# TB-S5D5_p03_MCU-v1_2.net
KiCad netlist of a schematic drawn in Altium Designer
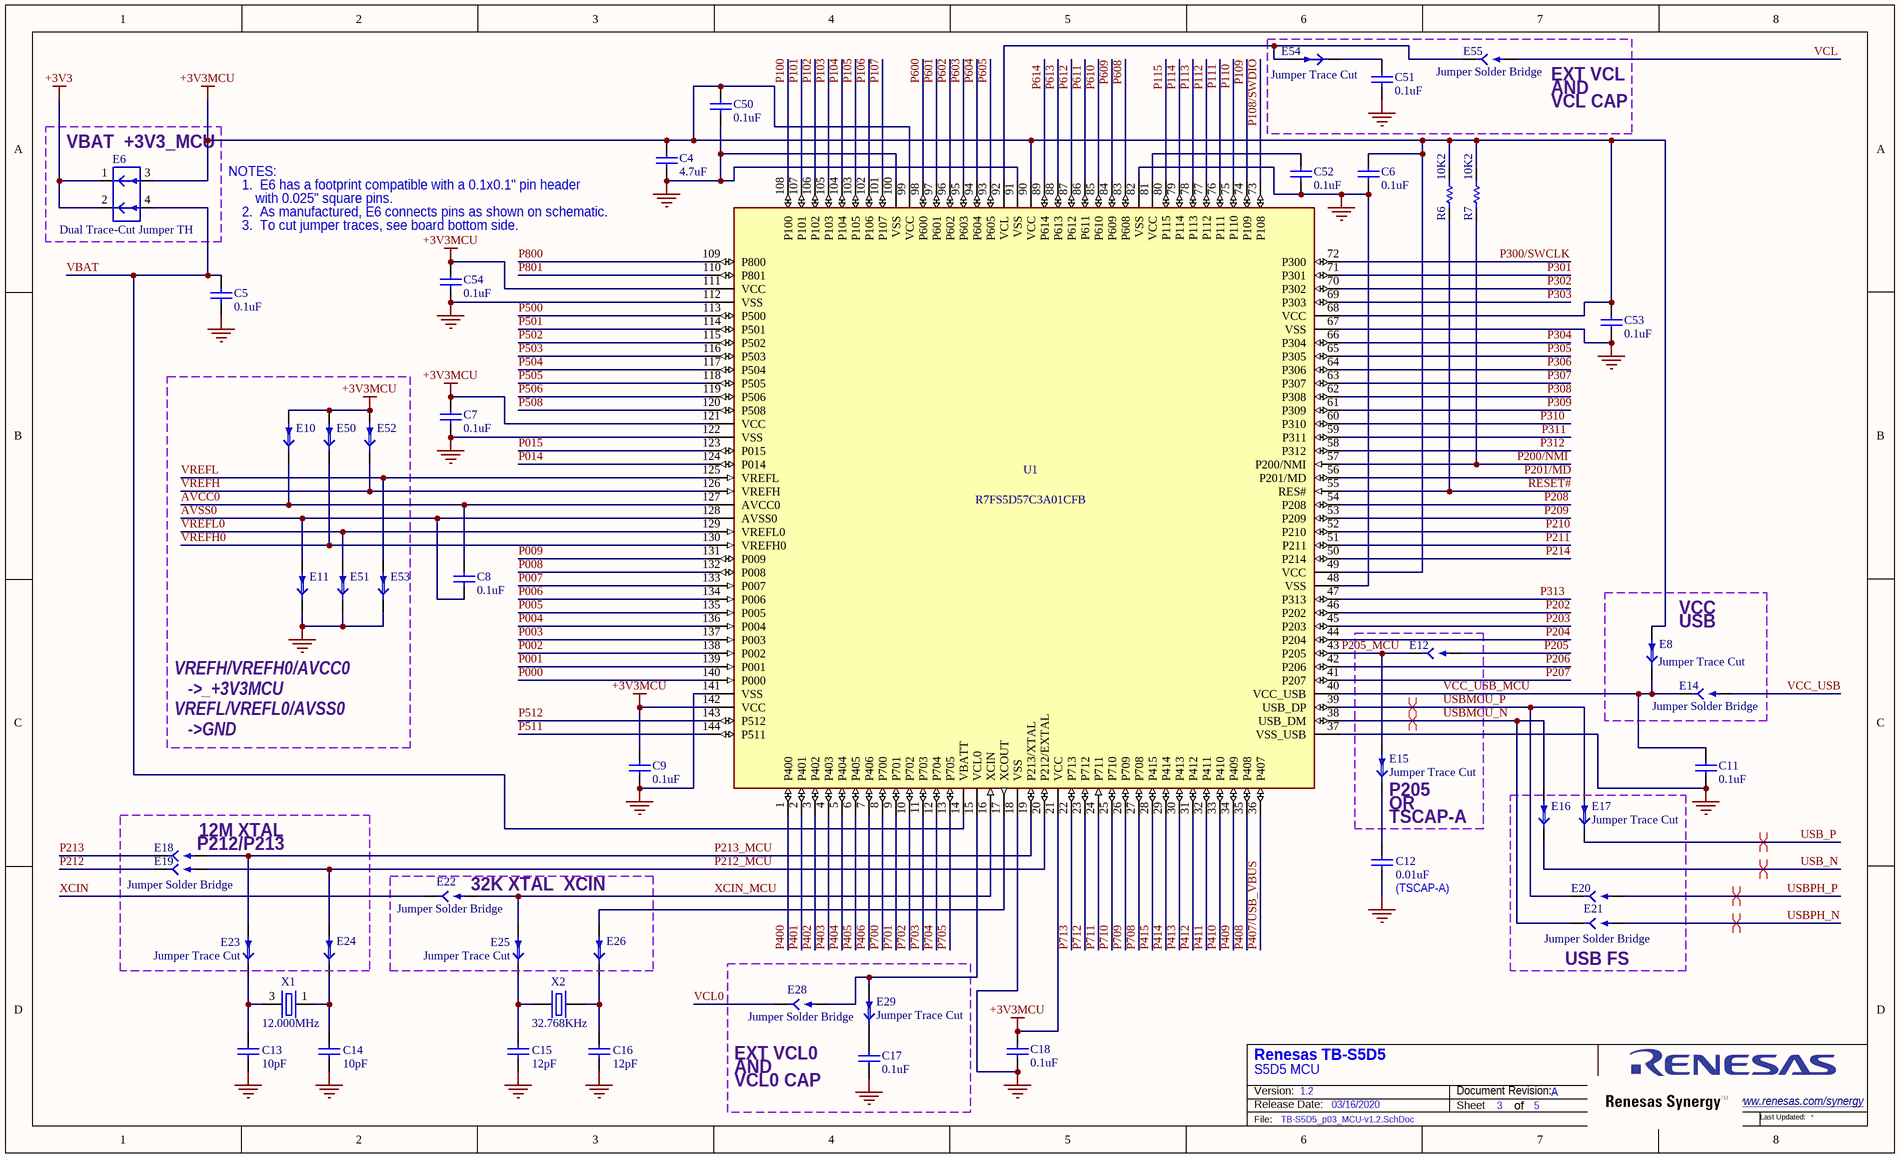
[diagram p0: TB-S5D5_p03_MCU-v1.2.SchDoc]

(export (version "E")
  (design (tool "Eeschema 10.0.6"))
  (components
    (comp (ref "C4")
      (value "CAP-000043-01")
      (footprint "CAPC0603-01")
      (description "Ceramic Chip Capacitor 0603 4.7uF 6.3V")
      (fields
        (field (name "MANUFACTURER") "Samsung")
        (field (name "MFG PART NUMBER") "CL10A475KQ8NNNL")
        (field (name "CAPACITANCE") "4.7uF")
      )
      (libsource (lib "Capacitors") (part "CAP-000043-01"))
    )
    (comp (ref "C5")
      (value "CAP-000029-01")
      (footprint "CAPC0603-01")
      (description "Ceramic Chip Capacitor 0603 0.1uF 50V")
      (fields
        (field (name "MANUFACTURER") "Samsung")
        (field (name "MFG PART NUMBER") "CL10B104KB8NNNC")
        (field (name "CAPACITANCE") "0.1uF")
      )
      (libsource (lib "Capacitors") (part "CAP-000029-01"))
    )
    (comp (ref "C6")
      (value "CAP-000029-01")
      (footprint "CAPC0603-01")
      (description "Ceramic Chip Capacitor 0603 0.1uF 50V")
      (fields
        (field (name "MANUFACTURER") "Samsung")
        (field (name "MFG PART NUMBER") "CL10B104KB8NNNC")
        (field (name "CAPACITANCE") "0.1uF")
      )
      (libsource (lib "Capacitors") (part "CAP-000029-01"))
    )
    (comp (ref "C7")
      (value "CAP-000029-01")
      (footprint "CAPC0603-01")
      (description "Ceramic Chip Capacitor 0603 0.1uF 50V")
      (fields
        (field (name "MANUFACTURER") "Samsung")
        (field (name "MFG PART NUMBER") "CL10B104KB8NNNC")
        (field (name "CAPACITANCE") "0.1uF")
      )
      (libsource (lib "Capacitors") (part "CAP-000029-01"))
    )
    (comp (ref "C8")
      (value "CAP-000029-01")
      (footprint "CAPC0603-01")
      (description "Ceramic Chip Capacitor 0603 0.1uF 50V")
      (fields
        (field (name "MANUFACTURER") "Samsung")
        (field (name "MFG PART NUMBER") "CL10B104KB8NNNC")
        (field (name "CAPACITANCE") "0.1uF")
      )
      (libsource (lib "Capacitors") (part "CAP-000029-01"))
    )
    (comp (ref "C9")
      (value "CAP-000029-01")
      (footprint "CAPC0603-01")
      (description "Ceramic Chip Capacitor 0603 0.1uF 50V")
      (fields
        (field (name "MANUFACTURER") "Samsung")
        (field (name "MFG PART NUMBER") "CL10B104KB8NNNC")
        (field (name "CAPACITANCE") "0.1uF")
      )
      (libsource (lib "Capacitors") (part "CAP-000029-01"))
    )
    (comp (ref "C11")
      (value "CAP-000029-01")
      (footprint "CAPC0603-01")
      (description "Ceramic Chip Capacitor 0603 0.1uF 50V")
      (fields
        (field (name "MANUFACTURER") "Samsung")
        (field (name "MFG PART NUMBER") "CL10B104KB8NNNC")
        (field (name "CAPACITANCE") "0.1uF")
      )
      (libsource (lib "Capacitors") (part "CAP-000029-01"))
    )
    (comp (ref "C12")
      (value "CAP-000062-01")
      (footprint "CAPC0402-01")
      (description "Ceramic Chip Capacitor 0402 0.01uF 50V")
      (fields
        (field (name "MANUFACTURER") "Samsung")
        (field (name "MFG PART NUMBER") "CL05B103KB5NNNC")
        (field (name "CAPACITANCE") "0.01uF")
      )
      (libsource (lib "Capacitors") (part "CAP-000062-01"))
    )
    (comp (ref "C13")
      (value "CAP-000081-01")
      (footprint "CAPC0201-01")
      (description "Ceramic Chip Capacitor 0201 10pF 25V")
      (fields
        (field (name "MANUFACTURER") "Samsung")
        (field (name "MFG PART NUMBER") "CL03C100DA3GNNC")
        (field (name "CAPACITANCE") "10pF")
      )
      (libsource (lib "Capacitors") (part "CAP-000081-01"))
    )
    (comp (ref "C14")
      (value "CAP-000081-01")
      (footprint "CAPC0201-01")
      (description "Ceramic Chip Capacitor 0201 10pF 25V")
      (fields
        (field (name "MANUFACTURER") "Samsung")
        (field (name "MFG PART NUMBER") "CL03C100DA3GNNC")
        (field (name "CAPACITANCE") "10pF")
      )
      (libsource (lib "Capacitors") (part "CAP-000081-01"))
    )
    (comp (ref "C15")
      (value "CAP-000059-01")
      (footprint "CAPC0402-01")
      (description "Ceramic Chip Capacitor 0402 12pF 50V")
      (fields
        (field (name "MANUFACTURER") "Samsung")
        (field (name "MFG PART NUMBER") "CL05C120JB5NNNC")
        (field (name "CAPACITANCE") "12pF")
      )
      (libsource (lib "Capacitors") (part "CAP-000059-01"))
    )
    (comp (ref "C16")
      (value "CAP-000059-01")
      (footprint "CAPC0402-01")
      (description "Ceramic Chip Capacitor 0402 12pF 50V")
      (fields
        (field (name "MANUFACTURER") "Samsung")
        (field (name "MFG PART NUMBER") "CL05C120JB5NNNC")
        (field (name "CAPACITANCE") "12pF")
      )
      (libsource (lib "Capacitors") (part "CAP-000059-01"))
    )
    (comp (ref "C17")
      (value "CAP-000029-01")
      (footprint "CAPC0603-01")
      (description "Ceramic Chip Capacitor 0603 0.1uF 50V")
      (fields
        (field (name "MANUFACTURER") "Samsung")
        (field (name "MFG PART NUMBER") "CL10B104KB8NNNC")
        (field (name "CAPACITANCE") "0.1uF")
      )
      (libsource (lib "Capacitors") (part "CAP-000029-01"))
    )
    (comp (ref "C18")
      (value "CAP-000029-01")
      (footprint "CAPC0603-01")
      (description "Ceramic Chip Capacitor 0603 0.1uF 50V")
      (fields
        (field (name "MANUFACTURER") "Samsung")
        (field (name "MFG PART NUMBER") "CL10B104KB8NNNC")
        (field (name "CAPACITANCE") "0.1uF")
      )
      (libsource (lib "Capacitors") (part "CAP-000029-01"))
    )
    (comp (ref "C50")
      (value "CAP-000029-01")
      (footprint "CAPC0603-01")
      (description "Ceramic Chip Capacitor 0603 0.1uF 50V")
      (fields
        (field (name "MANUFACTURER") "Samsung")
        (field (name "MFG PART NUMBER") "CL10B104KB8NNNC")
        (field (name "CAPACITANCE") "0.1uF")
      )
      (libsource (lib "Capacitors") (part "CAP-000029-01"))
    )
    (comp (ref "C51")
      (value "CAP-000029-01")
      (footprint "CAPC0603-01")
      (description "Ceramic Chip Capacitor 0603 0.1uF 50V")
      (fields
        (field (name "MANUFACTURER") "Samsung")
        (field (name "MFG PART NUMBER") "CL10B104KB8NNNC")
        (field (name "CAPACITANCE") "0.1uF")
      )
      (libsource (lib "Capacitors") (part "CAP-000029-01"))
    )
    (comp (ref "C52")
      (value "CAP-000029-01")
      (footprint "CAPC0603-01")
      (description "Ceramic Chip Capacitor 0603 0.1uF 50V")
      (fields
        (field (name "MANUFACTURER") "Samsung")
        (field (name "MFG PART NUMBER") "CL10B104KB8NNNC")
        (field (name "CAPACITANCE") "0.1uF")
      )
      (libsource (lib "Capacitors") (part "CAP-000029-01"))
    )
    (comp (ref "C53")
      (value "CAP-000029-01")
      (footprint "CAPC0603-01")
      (description "Ceramic Chip Capacitor 0603 0.1uF 50V")
      (fields
        (field (name "MANUFACTURER") "Samsung")
        (field (name "MFG PART NUMBER") "CL10B104KB8NNNC")
        (field (name "CAPACITANCE") "0.1uF")
      )
      (libsource (lib "Capacitors") (part "CAP-000029-01"))
    )
    (comp (ref "C54")
      (value "CAP-000029-01")
      (footprint "CAPC0603-01")
      (description "Ceramic Chip Capacitor 0603 0.1uF 50V")
      (fields
        (field (name "MANUFACTURER") "Samsung")
        (field (name "MFG PART NUMBER") "CL10B104KB8NNNC")
        (field (name "CAPACITANCE") "0.1uF")
      )
      (libsource (lib "Capacitors") (part "CAP-000029-01"))
    )
    (comp (ref "E6")
      (value "Dual Trace-Cut Jumper TH")
      (footprint "E_2x2pTH-TC100mil")
      (description "Trace-Cut Jumper pair, pins 1->3 & 2->4 connected")
      (libsource (lib "TB_SpecialLib") (part "E_JmpTCx2"))
    )
    (comp (ref "E8")
      (value "Jumper Trace Cut")
      (footprint "E_PadsTraceCut0805")
      (description "Pads on PCB with Trace Between for Cutting to isolate")
      (libsource (lib "TB_SpecialLib") (part "E_JmpTraceCut"))
    )
    (comp (ref "E10")
      (value "Jumper Trace Cut")
      (footprint "E_PadsTraceCut0805")
      (description "Pads on PCB with Trace Between for Cutting to isolate")
      (libsource (lib "TB_SpecialLib") (part "E_JmpTraceCut"))
    )
    (comp (ref "E11")
      (value "Jumper Trace Cut")
      (footprint "E_PadsTraceCut0805")
      (description "Pads on PCB with Trace Between for Cutting to isolate")
      (libsource (lib "TB_SpecialLib") (part "E_JmpTraceCut"))
    )
    (comp (ref "E12")
      (value "Jumper Solder Bridge")
      (footprint "E_PadsSplit0805")
      (description "Pads on PCB with Narrow Gap to allow Solder Bridging")
      (libsource (lib "TB_SpecialLib") (part "E_JmpSldrBridge"))
    )
    (comp (ref "E14")
      (value "Jumper Solder Bridge")
      (footprint "E_PadsSplit0805")
      (description "Pads on PCB with Narrow Gap to allow Solder Bridging")
      (libsource (lib "TB_SpecialLib") (part "E_JmpSldrBridge"))
    )
    (comp (ref "E15")
      (value "Jumper Trace Cut")
      (footprint "E_PadsTraceCut0805")
      (description "Pads on PCB with Trace Between for Cutting to isolate")
      (libsource (lib "TB_SpecialLib") (part "E_JmpTraceCut"))
    )
    (comp (ref "E16")
      (value "Jumper Trace Cut")
      (footprint "E_PadsTraceCut0805")
      (description "Pads on PCB with Trace Between for Cutting to isolate")
      (libsource (lib "TB_SpecialLib") (part "E_JmpTraceCut"))
    )
    (comp (ref "E17")
      (value "Jumper Trace Cut")
      (footprint "E_PadsTraceCut0805")
      (description "Pads on PCB with Trace Between for Cutting to isolate")
      (libsource (lib "TB_SpecialLib") (part "E_JmpTraceCut"))
    )
    (comp (ref "E18")
      (value "Jumper Solder Bridge")
      (footprint "E_PadsSplit0805")
      (description "Pads on PCB with Narrow Gap to allow Solder Bridging")
      (libsource (lib "TB_SpecialLib") (part "E_JmpSldrBridge"))
    )
    (comp (ref "E19")
      (value "Jumper Solder Bridge")
      (footprint "E_PadsSplit0805")
      (description "Pads on PCB with Narrow Gap to allow Solder Bridging")
      (libsource (lib "TB_SpecialLib") (part "E_JmpSldrBridge"))
    )
    (comp (ref "E20")
      (value "Jumper Solder Bridge")
      (footprint "E_PadsSplit0805")
      (description "Pads on PCB with Narrow Gap to allow Solder Bridging")
      (libsource (lib "TB_SpecialLib") (part "E_JmpSldrBridge"))
    )
    (comp (ref "E21")
      (value "Jumper Solder Bridge")
      (footprint "E_PadsSplit0805")
      (description "Pads on PCB with Narrow Gap to allow Solder Bridging")
      (libsource (lib "TB_SpecialLib") (part "E_JmpSldrBridge"))
    )
    (comp (ref "E22")
      (value "Jumper Solder Bridge")
      (footprint "E_PadsSplit0805")
      (description "Pads on PCB with Narrow Gap to allow Solder Bridging")
      (libsource (lib "TB_SpecialLib") (part "E_JmpSldrBridge"))
    )
    (comp (ref "E23")
      (value "Jumper Trace Cut")
      (footprint "E_PadsTraceCut0805")
      (description "Pads on PCB with Trace Between for Cutting to isolate")
      (libsource (lib "TB_SpecialLib") (part "E_JmpTraceCut"))
    )
    (comp (ref "E24")
      (value "Jumper Trace Cut")
      (footprint "E_PadsTraceCut0805")
      (description "Pads on PCB with Trace Between for Cutting to isolate")
      (libsource (lib "TB_SpecialLib") (part "E_JmpTraceCut"))
    )
    (comp (ref "E25")
      (value "Jumper Trace Cut")
      (footprint "E_PadsTraceCut0805")
      (description "Pads on PCB with Trace Between for Cutting to isolate")
      (libsource (lib "TB_SpecialLib") (part "E_JmpTraceCut"))
    )
    (comp (ref "E26")
      (value "Jumper Trace Cut")
      (footprint "E_PadsTraceCut0805")
      (description "Pads on PCB with Trace Between for Cutting to isolate")
      (libsource (lib "TB_SpecialLib") (part "E_JmpTraceCut"))
    )
    (comp (ref "E28")
      (value "Jumper Solder Bridge")
      (footprint "E_PadsSplit0805")
      (description "Pads on PCB with Narrow Gap to allow Solder Bridging")
      (libsource (lib "TB_SpecialLib") (part "E_JmpSldrBridge"))
    )
    (comp (ref "E29")
      (value "Jumper Trace Cut")
      (footprint "E_PadsTraceCut0805")
      (description "Pads on PCB with Trace Between for Cutting to isolate")
      (libsource (lib "TB_SpecialLib") (part "E_JmpTraceCut"))
    )
    (comp (ref "E50")
      (value "Jumper Trace Cut")
      (footprint "E_PadsTraceCut0805")
      (description "Pads on PCB with Trace Between for Cutting to isolate")
      (libsource (lib "TB_SpecialLib") (part "E_JmpTraceCut"))
    )
    (comp (ref "E51")
      (value "Jumper Trace Cut")
      (footprint "E_PadsTraceCut0805")
      (description "Pads on PCB with Trace Between for Cutting to isolate")
      (libsource (lib "TB_SpecialLib") (part "E_JmpTraceCut"))
    )
    (comp (ref "E52")
      (value "Jumper Trace Cut")
      (footprint "E_PadsTraceCut0805")
      (description "Pads on PCB with Trace Between for Cutting to isolate")
      (libsource (lib "TB_SpecialLib") (part "E_JmpTraceCut"))
    )
    (comp (ref "E53")
      (value "Jumper Trace Cut")
      (footprint "E_PadsTraceCut0805")
      (description "Pads on PCB with Trace Between for Cutting to isolate")
      (libsource (lib "TB_SpecialLib") (part "E_JmpTraceCut"))
    )
    (comp (ref "E54")
      (value "Jumper Trace Cut")
      (footprint "E_PadsTraceCut0805")
      (description "Pads on PCB with Trace Between for Cutting to isolate")
      (libsource (lib "TB_SpecialLib") (part "E_JmpTraceCut"))
    )
    (comp (ref "E55")
      (value "Jumper Solder Bridge")
      (footprint "E_PadsSplit0805")
      (description "Pads on PCB with Narrow Gap to allow Solder Bridging")
      (libsource (lib "TB_SpecialLib") (part "E_JmpSldrBridge"))
    )
    (comp (ref "R6")
      (value "RES-000091-01")
      (footprint "RESC0603-01")
      (description "Chip Resistor Thick Film 0603 10K2 1% 1/10W")
      (fields
        (field (name "MANUFACTURER") "NIC")
        (field (name "MFG PART NUMBER") "NRC06F1022TRF")
        (field (name "RESISTANCE") "10K2")
      )
      (libsource (lib "Resistors") (part "RES-000091-01"))
    )
    (comp (ref "R7")
      (value "RES-000091-01")
      (footprint "RESC0603-01")
      (description "Chip Resistor Thick Film 0603 10K2 1% 1/10W")
      (fields
        (field (name "MANUFACTURER") "NIC")
        (field (name "MFG PART NUMBER") "NRC06F1022TRF")
        (field (name "RESISTANCE") "10K2")
      )
      (libsource (lib "Resistors") (part "RES-000091-01"))
    )
    (comp (ref "U1")
      (value "ICN-R01001-01")
      (footprint "RENESAS_PLQP0144KA-B_N")
      (description "Renesas S5D5 ARM Cortex M4 120MHz MCU LQFP144")
      (fields
        (field (name "MANUFACTURER") "Renesas")
        (field (name "MFG PART NUMBER") "R7FS5D57C3A01CFB#AA0")
        (field (name "DISPLAY NAME") "R7FS5D57C3A01CFB")
      )
      (libsource (lib "SpecialPartsLib") (part "ICN-R01001-01"))
    )
    (comp (ref "X1")
      (value "XTL-000011-01")
      (footprint "TXC_7V")
      (description "Crystal 12MHz 10pF")
      (fields
        (field (name "MANUFACTURER") "Abracon")
        (field (name "MFG PART NUMBER") "ABM8G-12.000MHZ-B4Y-T")
        (field (name "FREQUENCY") "12.000MHz")
      )
      (libsource (lib "Misc") (part "XTL-000011-01"))
    )
    (comp (ref "X2")
      (value "XTL-000006-01")
      (footprint "ABRACON_ABS07")
      (description "Crystal 32.769KHz 12.5pF SMT")
      (fields
        (field (name "MANUFACTURER") "Abracon")
        (field (name "MFG PART NUMBER") "ABS07-32.768KHZ-T")
        (field (name "FREQUENCY") "32.768KHz")
      )
      (libsource (lib "Misc") (part "XTL-000006-01"))
    )
  )
  (nets
    (net (code "1") (name "+3V3") (class "Default")
      (node (ref "E6") (pin "1") (pinfunction "A1_1") (pintype "passive"))
      (node (ref "E6") (pin "2") (pinfunction "A2_2") (pintype "passive"))
    )
    (net (code "2") (name "+3V3MCU") (class "Default")
      (node (ref "C18") (pin "1") (pinfunction "1_1") (pintype "passive"))
      (node (ref "C4") (pin "2") (pinfunction "2_2") (pintype "passive"))
      (node (ref "C50") (pin "1") (pinfunction "1_1") (pintype "passive"))
      (node (ref "C53") (pin "1") (pinfunction "1_1") (pintype "passive"))
      (node (ref "C54") (pin "1") (pinfunction "1_1") (pintype "passive"))
      (node (ref "C6") (pin "1") (pinfunction "1_1") (pintype "passive"))
      (node (ref "C7") (pin "1") (pinfunction "1_1") (pintype "passive"))
      (node (ref "C9") (pin "1") (pinfunction "1_1") (pintype "passive"))
      (node (ref "E10") (pin "2") (pinfunction "A_2") (pintype "passive"))
      (node (ref "E50") (pin "2") (pinfunction "A_2") (pintype "passive"))
      (node (ref "E52") (pin "2") (pinfunction "A_2") (pintype "passive"))
      (node (ref "E6") (pin "3") (pinfunction "B1_3") (pintype "passive"))
      (node (ref "E8") (pin "2") (pinfunction "A_2") (pintype "passive"))
      (node (ref "R6") (pin "2") (pinfunction "2_2") (pintype "passive"))
      (node (ref "R7") (pin "2") (pinfunction "2_2") (pintype "passive"))
      (node (ref "U1") (pin "111") (pinfunction "VCC_111") (pintype "power_in"))
      (node (ref "U1") (pin "121") (pinfunction "VCC_121") (pintype "power_in"))
      (node (ref "U1") (pin "142") (pinfunction "VCC_142") (pintype "power_in"))
      (node (ref "U1") (pin "21") (pinfunction "VCC_21") (pintype "power_in"))
      (node (ref "U1") (pin "49") (pinfunction "VCC_49") (pintype "power_in"))
      (node (ref "U1") (pin "68") (pinfunction "VCC_68") (pintype "power_in"))
      (node (ref "U1") (pin "90") (pinfunction "VCC_90") (pintype "power_in"))
      (node (ref "U1") (pin "99") (pinfunction "VCC_99") (pintype "power_in"))
    )
    (net (code "3") (name "/AVCC0") (class "Default")
      (node (ref "C8") (pin "1") (pinfunction "1_1") (pintype "passive"))
      (node (ref "E10") (pin "1") (pinfunction "A_1") (pintype "passive"))
      (node (ref "U1") (pin "127") (pinfunction "AVCC0_127") (pintype "power_in"))
    )
    (net (code "4") (name "/AVSS0") (class "Default")
      (node (ref "C8") (pin "2") (pinfunction "2_2") (pintype "passive"))
      (node (ref "E11") (pin "2") (pinfunction "A_2") (pintype "passive"))
      (node (ref "U1") (pin "128") (pinfunction "AVSS0_128") (pintype "power_in"))
    )
    (net (code "5") (name "/P000") (class "Default")
      (node (ref "U1") (pin "140") (pinfunction "P000_140") (pintype "input"))
    )
    (net (code "6") (name "/P001") (class "Default")
      (node (ref "U1") (pin "139") (pinfunction "P001_139") (pintype "input"))
    )
    (net (code "7") (name "/P002") (class "Default")
      (node (ref "U1") (pin "138") (pinfunction "P002_138") (pintype "input"))
    )
    (net (code "8") (name "/P003") (class "Default")
      (node (ref "U1") (pin "137") (pinfunction "P003_137") (pintype "input"))
    )
    (net (code "9") (name "/P004") (class "Default")
      (node (ref "U1") (pin "136") (pinfunction "P004_136") (pintype "input"))
    )
    (net (code "10") (name "/P005") (class "Default")
      (node (ref "U1") (pin "135") (pinfunction "P005_135") (pintype "input"))
    )
    (net (code "11") (name "/P006") (class "Default")
      (node (ref "U1") (pin "134") (pinfunction "P006_134") (pintype "input"))
    )
    (net (code "12") (name "/P007") (class "Default")
      (node (ref "U1") (pin "133") (pinfunction "P007_133") (pintype "input"))
    )
    (net (code "13") (name "/P008") (class "Default")
      (node (ref "U1") (pin "132") (pinfunction "P008_132") (pintype "bidirectional"))
    )
    (net (code "14") (name "/P009") (class "Default")
      (node (ref "U1") (pin "131") (pinfunction "P009_131") (pintype "bidirectional"))
    )
    (net (code "15") (name "/P014") (class "Default")
      (node (ref "U1") (pin "124") (pinfunction "P014_124") (pintype "bidirectional"))
    )
    (net (code "16") (name "/P015") (class "Default")
      (node (ref "U1") (pin "123") (pinfunction "P015_123") (pintype "bidirectional"))
    )
    (net (code "17") (name "/P100") (class "Default")
      (node (ref "U1") (pin "108") (pinfunction "P100_108") (pintype "bidirectional"))
    )
    (net (code "18") (name "/P101") (class "Default")
      (node (ref "U1") (pin "107") (pinfunction "P101_107") (pintype "bidirectional"))
    )
    (net (code "19") (name "/P102") (class "Default")
      (node (ref "U1") (pin "106") (pinfunction "P102_106") (pintype "bidirectional"))
    )
    (net (code "20") (name "/P103") (class "Default")
      (node (ref "U1") (pin "105") (pinfunction "P103_105") (pintype "bidirectional"))
    )
    (net (code "21") (name "/P104") (class "Default")
      (node (ref "U1") (pin "104") (pinfunction "P104_104") (pintype "bidirectional"))
    )
    (net (code "22") (name "/P105") (class "Default")
      (node (ref "U1") (pin "103") (pinfunction "P105_103") (pintype "bidirectional"))
    )
    (net (code "23") (name "/P106") (class "Default")
      (node (ref "U1") (pin "102") (pinfunction "P106_102") (pintype "bidirectional"))
    )
    (net (code "24") (name "/P107") (class "Default")
      (node (ref "U1") (pin "101") (pinfunction "P107_101") (pintype "bidirectional"))
    )
    (net (code "25") (name "/P108{slash}SWDIO") (class "Default")
      (node (ref "U1") (pin "73") (pinfunction "P108_73") (pintype "bidirectional"))
    )
    (net (code "26") (name "/P109") (class "Default")
      (node (ref "U1") (pin "74") (pinfunction "P109_74") (pintype "bidirectional"))
    )
    (net (code "27") (name "/P110") (class "Default")
      (node (ref "U1") (pin "75") (pinfunction "P110_75") (pintype "bidirectional"))
    )
    (net (code "28") (name "/P111") (class "Default")
      (node (ref "U1") (pin "76") (pinfunction "P111_76") (pintype "bidirectional"))
    )
    (net (code "29") (name "/P112") (class "Default")
      (node (ref "U1") (pin "77") (pinfunction "P112_77") (pintype "bidirectional"))
    )
    (net (code "30") (name "/P113") (class "Default")
      (node (ref "U1") (pin "78") (pinfunction "P113_78") (pintype "bidirectional"))
    )
    (net (code "31") (name "/P114") (class "Default")
      (node (ref "U1") (pin "79") (pinfunction "P114_79") (pintype "bidirectional"))
    )
    (net (code "32") (name "/P115") (class "Default")
      (node (ref "U1") (pin "80") (pinfunction "P115_80") (pintype "bidirectional"))
    )
    (net (code "33") (name "/P200{slash}NMI") (class "Default")
      (node (ref "R7") (pin "1") (pinfunction "1_1") (pintype "passive"))
      (node (ref "U1") (pin "57") (pinfunction "P200/NMI_57") (pintype "input"))
    )
    (net (code "34") (name "/P201{slash}MD") (class "Default")
      (node (ref "U1") (pin "56") (pinfunction "P201/MD_56") (pintype "bidirectional"))
    )
    (net (code "35") (name "/P202") (class "Default")
      (node (ref "U1") (pin "46") (pinfunction "P202_46") (pintype "bidirectional"))
    )
    (net (code "36") (name "/P203") (class "Default")
      (node (ref "U1") (pin "45") (pinfunction "P203_45") (pintype "bidirectional"))
    )
    (net (code "37") (name "/P204") (class "Default")
      (node (ref "U1") (pin "44") (pinfunction "P204_44") (pintype "bidirectional"))
    )
    (net (code "38") (name "/P205") (class "Default")
      (node (ref "E12") (pin "2") (pinfunction "A_2") (pintype "passive"))
    )
    (net (code "39") (name "/P205_MCU") (class "Default")
      (node (ref "E12") (pin "1") (pinfunction "A_1") (pintype "passive"))
      (node (ref "E15") (pin "2") (pinfunction "A_2") (pintype "passive"))
      (node (ref "U1") (pin "43") (pinfunction "P205_43") (pintype "bidirectional"))
    )
    (net (code "40") (name "/P206") (class "Default")
      (node (ref "U1") (pin "42") (pinfunction "P206_42") (pintype "bidirectional"))
    )
    (net (code "41") (name "/P207") (class "Default")
      (node (ref "U1") (pin "41") (pinfunction "P207_41") (pintype "bidirectional"))
    )
    (net (code "42") (name "/P208") (class "Default")
      (node (ref "U1") (pin "54") (pinfunction "P208_54") (pintype "bidirectional"))
    )
    (net (code "43") (name "/P209") (class "Default")
      (node (ref "U1") (pin "53") (pinfunction "P209_53") (pintype "bidirectional"))
    )
    (net (code "44") (name "/P210") (class "Default")
      (node (ref "U1") (pin "52") (pinfunction "P210_52") (pintype "bidirectional"))
    )
    (net (code "45") (name "/P211") (class "Default")
      (node (ref "U1") (pin "51") (pinfunction "P211_51") (pintype "bidirectional"))
    )
    (net (code "46") (name "/P212") (class "Default")
      (node (ref "E19") (pin "1") (pinfunction "A_1") (pintype "passive"))
    )
    (net (code "47") (name "/P212_MCU") (class "Default")
      (node (ref "E19") (pin "2") (pinfunction "A_2") (pintype "passive"))
      (node (ref "E24") (pin "2") (pinfunction "A_2") (pintype "passive"))
      (node (ref "U1") (pin "20") (pinfunction "P212/EXTAL_20") (pintype "bidirectional"))
    )
    (net (code "48") (name "/P213") (class "Default")
      (node (ref "E18") (pin "1") (pinfunction "A_1") (pintype "passive"))
    )
    (net (code "49") (name "/P213_MCU") (class "Default")
      (node (ref "E18") (pin "2") (pinfunction "A_2") (pintype "passive"))
      (node (ref "E23") (pin "2") (pinfunction "A_2") (pintype "passive"))
      (node (ref "U1") (pin "19") (pinfunction "P213/XTAL_19") (pintype "bidirectional"))
    )
    (net (code "50") (name "/P214") (class "Default")
      (node (ref "U1") (pin "50") (pinfunction "P214_50") (pintype "bidirectional"))
    )
    (net (code "51") (name "/P300{slash}SWCLK") (class "Default")
      (node (ref "U1") (pin "72") (pinfunction "P300_72") (pintype "bidirectional"))
    )
    (net (code "52") (name "/P301") (class "Default")
      (node (ref "U1") (pin "71") (pinfunction "P301_71") (pintype "bidirectional"))
    )
    (net (code "53") (name "/P302") (class "Default")
      (node (ref "U1") (pin "70") (pinfunction "P302_70") (pintype "bidirectional"))
    )
    (net (code "54") (name "/P303") (class "Default")
      (node (ref "U1") (pin "69") (pinfunction "P303_69") (pintype "bidirectional"))
    )
    (net (code "55") (name "/P304") (class "Default")
      (node (ref "U1") (pin "66") (pinfunction "P304_66") (pintype "bidirectional"))
    )
    (net (code "56") (name "/P305") (class "Default")
      (node (ref "U1") (pin "65") (pinfunction "P305_65") (pintype "bidirectional"))
    )
    (net (code "57") (name "/P306") (class "Default")
      (node (ref "U1") (pin "64") (pinfunction "P306_64") (pintype "bidirectional"))
    )
    (net (code "58") (name "/P307") (class "Default")
      (node (ref "U1") (pin "63") (pinfunction "P307_63") (pintype "bidirectional"))
    )
    (net (code "59") (name "/P308") (class "Default")
      (node (ref "U1") (pin "62") (pinfunction "P308_62") (pintype "bidirectional"))
    )
    (net (code "60") (name "/P309") (class "Default")
      (node (ref "U1") (pin "61") (pinfunction "P309_61") (pintype "bidirectional"))
    )
    (net (code "61") (name "/P310") (class "Default")
      (node (ref "U1") (pin "60") (pinfunction "P310_60") (pintype "bidirectional"))
    )
    (net (code "62") (name "/P311") (class "Default")
      (node (ref "U1") (pin "59") (pinfunction "P311_59") (pintype "bidirectional"))
    )
    (net (code "63") (name "/P312") (class "Default")
      (node (ref "U1") (pin "58") (pinfunction "P312_58") (pintype "bidirectional"))
    )
    (net (code "64") (name "/P313") (class "Default")
      (node (ref "U1") (pin "47") (pinfunction "P313_47") (pintype "bidirectional"))
    )
    (net (code "65") (name "/P400") (class "Default")
      (node (ref "U1") (pin "1") (pinfunction "P400_1") (pintype "bidirectional"))
    )
    (net (code "66") (name "/P401") (class "Default")
      (node (ref "U1") (pin "2") (pinfunction "P401_2") (pintype "bidirectional"))
    )
    (net (code "67") (name "/P402") (class "Default")
      (node (ref "U1") (pin "3") (pinfunction "P402_3") (pintype "bidirectional"))
    )
    (net (code "68") (name "/P403") (class "Default")
      (node (ref "U1") (pin "4") (pinfunction "P403_4") (pintype "bidirectional"))
    )
    (net (code "69") (name "/P404") (class "Default")
      (node (ref "U1") (pin "5") (pinfunction "P404_5") (pintype "bidirectional"))
    )
    (net (code "70") (name "/P405") (class "Default")
      (node (ref "U1") (pin "6") (pinfunction "P405_6") (pintype "bidirectional"))
    )
    (net (code "71") (name "/P406") (class "Default")
      (node (ref "U1") (pin "7") (pinfunction "P406_7") (pintype "bidirectional"))
    )
    (net (code "72") (name "/P407{slash}USB_VBUS") (class "Default")
      (node (ref "U1") (pin "36") (pinfunction "P407_36") (pintype "bidirectional"))
    )
    (net (code "73") (name "/P408") (class "Default")
      (node (ref "U1") (pin "35") (pinfunction "P408_35") (pintype "bidirectional"))
    )
    (net (code "74") (name "/P409") (class "Default")
      (node (ref "U1") (pin "34") (pinfunction "P409_34") (pintype "bidirectional"))
    )
    (net (code "75") (name "/P410") (class "Default")
      (node (ref "U1") (pin "33") (pinfunction "P410_33") (pintype "bidirectional"))
    )
    (net (code "76") (name "/P411") (class "Default")
      (node (ref "U1") (pin "32") (pinfunction "P411_32") (pintype "bidirectional"))
    )
    (net (code "77") (name "/P412") (class "Default")
      (node (ref "U1") (pin "31") (pinfunction "P412_31") (pintype "bidirectional"))
    )
    (net (code "78") (name "/P413") (class "Default")
      (node (ref "U1") (pin "30") (pinfunction "P413_30") (pintype "bidirectional"))
    )
    (net (code "79") (name "/P414") (class "Default")
      (node (ref "U1") (pin "29") (pinfunction "P414_29") (pintype "bidirectional"))
    )
    (net (code "80") (name "/P415") (class "Default")
      (node (ref "U1") (pin "28") (pinfunction "P415_28") (pintype "bidirectional"))
    )
    (net (code "81") (name "/P500") (class "Default")
      (node (ref "U1") (pin "113") (pinfunction "P500_113") (pintype "bidirectional"))
    )
    (net (code "82") (name "/P501") (class "Default")
      (node (ref "U1") (pin "114") (pinfunction "P501_114") (pintype "bidirectional"))
    )
    (net (code "83") (name "/P502") (class "Default")
      (node (ref "U1") (pin "115") (pinfunction "P502_115") (pintype "bidirectional"))
    )
    (net (code "84") (name "/P503") (class "Default")
      (node (ref "U1") (pin "116") (pinfunction "P503_116") (pintype "bidirectional"))
    )
    (net (code "85") (name "/P504") (class "Default")
      (node (ref "U1") (pin "117") (pinfunction "P504_117") (pintype "bidirectional"))
    )
    (net (code "86") (name "/P505") (class "Default")
      (node (ref "U1") (pin "118") (pinfunction "P505_118") (pintype "bidirectional"))
    )
    (net (code "87") (name "/P506") (class "Default")
      (node (ref "U1") (pin "119") (pinfunction "P506_119") (pintype "bidirectional"))
    )
    (net (code "88") (name "/P508") (class "Default")
      (node (ref "U1") (pin "120") (pinfunction "P508_120") (pintype "bidirectional"))
    )
    (net (code "89") (name "/P511") (class "Default")
      (node (ref "U1") (pin "144") (pinfunction "P511_144") (pintype "bidirectional"))
    )
    (net (code "90") (name "/P512") (class "Default")
      (node (ref "U1") (pin "143") (pinfunction "P512_143") (pintype "bidirectional"))
    )
    (net (code "91") (name "/P600") (class "Default")
      (node (ref "U1") (pin "98") (pinfunction "P600_98") (pintype "bidirectional"))
    )
    (net (code "92") (name "/P601") (class "Default")
      (node (ref "U1") (pin "97") (pinfunction "P601_97") (pintype "bidirectional"))
    )
    (net (code "93") (name "/P602") (class "Default")
      (node (ref "U1") (pin "96") (pinfunction "P602_96") (pintype "bidirectional"))
    )
    (net (code "94") (name "/P603") (class "Default")
      (node (ref "U1") (pin "95") (pinfunction "P603_95") (pintype "bidirectional"))
    )
    (net (code "95") (name "/P604") (class "Default")
      (node (ref "U1") (pin "94") (pinfunction "P604_94") (pintype "bidirectional"))
    )
    (net (code "96") (name "/P605") (class "Default")
      (node (ref "U1") (pin "93") (pinfunction "P605_93") (pintype "bidirectional"))
    )
    (net (code "97") (name "/P608") (class "Default")
      (node (ref "U1") (pin "83") (pinfunction "P608_83") (pintype "bidirectional"))
    )
    (net (code "98") (name "/P609") (class "Default")
      (node (ref "U1") (pin "84") (pinfunction "P609_84") (pintype "bidirectional"))
    )
    (net (code "99") (name "/P610") (class "Default")
      (node (ref "U1") (pin "85") (pinfunction "P610_85") (pintype "bidirectional"))
    )
    (net (code "100") (name "/P611") (class "Default")
      (node (ref "U1") (pin "86") (pinfunction "P611_86") (pintype "bidirectional"))
    )
    (net (code "101") (name "/P612") (class "Default")
      (node (ref "U1") (pin "87") (pinfunction "P612_87") (pintype "bidirectional"))
    )
    (net (code "102") (name "/P613") (class "Default")
      (node (ref "U1") (pin "88") (pinfunction "P613_88") (pintype "bidirectional"))
    )
    (net (code "103") (name "/P614") (class "Default")
      (node (ref "U1") (pin "89") (pinfunction "P614_89") (pintype "bidirectional"))
    )
    (net (code "104") (name "/P700") (class "Default")
      (node (ref "U1") (pin "8") (pinfunction "P700_8") (pintype "bidirectional"))
    )
    (net (code "105") (name "/P701") (class "Default")
      (node (ref "U1") (pin "9") (pinfunction "P701_9") (pintype "bidirectional"))
    )
    (net (code "106") (name "/P702") (class "Default")
      (node (ref "U1") (pin "10") (pinfunction "P702_10") (pintype "bidirectional"))
    )
    (net (code "107") (name "/P703") (class "Default")
      (node (ref "U1") (pin "11") (pinfunction "P703_11") (pintype "bidirectional"))
    )
    (net (code "108") (name "/P704") (class "Default")
      (node (ref "U1") (pin "12") (pinfunction "P704_12") (pintype "bidirectional"))
    )
    (net (code "109") (name "/P705") (class "Default")
      (node (ref "U1") (pin "13") (pinfunction "P705_13") (pintype "bidirectional"))
    )
    (net (code "110") (name "/P708") (class "Default")
      (node (ref "U1") (pin "27") (pinfunction "P708_27") (pintype "bidirectional"))
    )
    (net (code "111") (name "/P709") (class "Default")
      (node (ref "U1") (pin "26") (pinfunction "P709_26") (pintype "bidirectional"))
    )
    (net (code "112") (name "/P710") (class "Default")
      (node (ref "U1") (pin "25") (pinfunction "P710_25") (pintype "bidirectional"))
    )
    (net (code "113") (name "/P711") (class "Default")
      (node (ref "U1") (pin "24") (pinfunction "P711_24") (pintype "input"))
    )
    (net (code "114") (name "/P712") (class "Default")
      (node (ref "U1") (pin "23") (pinfunction "P712_23") (pintype "bidirectional"))
    )
    (net (code "115") (name "/P713") (class "Default")
      (node (ref "U1") (pin "22") (pinfunction "P713_22") (pintype "bidirectional"))
    )
    (net (code "116") (name "/P800") (class "Default")
      (node (ref "U1") (pin "109") (pinfunction "P800_109") (pintype "bidirectional"))
    )
    (net (code "117") (name "/P801") (class "Default")
      (node (ref "U1") (pin "110") (pinfunction "P801_110") (pintype "bidirectional"))
    )
    (net (code "118") (name "/RESET#") (class "Default")
      (node (ref "R6") (pin "1") (pinfunction "1_1") (pintype "passive"))
      (node (ref "U1") (pin "55") (pinfunction "RES#_55") (pintype "input"))
    )
    (net (code "119") (name "/USBMCU_N") (class "Default")
      (node (ref "E16") (pin "2") (pinfunction "A_2") (pintype "passive"))
      (node (ref "E21") (pin "1") (pinfunction "A_1") (pintype "passive"))
      (node (ref "U1") (pin "38") (pinfunction "USB_DM_38") (pintype "bidirectional"))
    )
    (net (code "120") (name "/USBMCU_P") (class "Default")
      (node (ref "E17") (pin "2") (pinfunction "A_2") (pintype "passive"))
      (node (ref "E20") (pin "1") (pinfunction "A_1") (pintype "passive"))
      (node (ref "U1") (pin "39") (pinfunction "USB_DP_39") (pintype "bidirectional"))
    )
    (net (code "121") (name "/USBPH_N") (class "Default")
      (node (ref "E21") (pin "2") (pinfunction "A_2") (pintype "passive"))
    )
    (net (code "122") (name "/USBPH_P") (class "Default")
      (node (ref "E20") (pin "2") (pinfunction "A_2") (pintype "passive"))
    )
    (net (code "123") (name "/USB_N") (class "Default")
      (node (ref "E16") (pin "1") (pinfunction "A_1") (pintype "passive"))
    )
    (net (code "124") (name "/USB_P") (class "Default")
      (node (ref "E17") (pin "1") (pinfunction "A_1") (pintype "passive"))
    )
    (net (code "125") (name "/VBAT") (class "Default")
      (node (ref "C5") (pin "1") (pinfunction "1_1") (pintype "passive"))
      (node (ref "E6") (pin "4") (pinfunction "B2_4") (pintype "passive"))
      (node (ref "U1") (pin "14") (pinfunction "VBATT_14") (pintype "power_in"))
    )
    (net (code "126") (name "/VCC_USB") (class "Default")
      (node (ref "E14") (pin "2") (pinfunction "A_2") (pintype "passive"))
    )
    (net (code "127") (name "/VCC_USB_MCU") (class "Default")
      (node (ref "C11") (pin "1") (pinfunction "1_1") (pintype "passive"))
      (node (ref "E14") (pin "1") (pinfunction "A_1") (pintype "passive"))
      (node (ref "E8") (pin "1") (pinfunction "A_1") (pintype "passive"))
      (node (ref "U1") (pin "40") (pinfunction "VCC_USB_40") (pintype "power_in"))
    )
    (net (code "128") (name "/VCL") (class "Default")
      (node (ref "E55") (pin "2") (pinfunction "A_2") (pintype "passive"))
    )
    (net (code "129") (name "/VCL0") (class "Default")
      (node (ref "E28") (pin "1") (pinfunction "A_1") (pintype "passive"))
    )
    (net (code "130") (name "/VREFH") (class "Default")
      (node (ref "E52") (pin "1") (pinfunction "A_1") (pintype "passive"))
      (node (ref "U1") (pin "126") (pinfunction "VREFH_126") (pintype "input"))
    )
    (net (code "131") (name "/VREFH0") (class "Default")
      (node (ref "E50") (pin "1") (pinfunction "A_1") (pintype "passive"))
      (node (ref "U1") (pin "130") (pinfunction "VREFH0_130") (pintype "input"))
    )
    (net (code "132") (name "/VREFL") (class "Default")
      (node (ref "E53") (pin "2") (pinfunction "A_2") (pintype "passive"))
      (node (ref "U1") (pin "125") (pinfunction "VREFL_125") (pintype "input"))
    )
    (net (code "133") (name "/VREFL0") (class "Default")
      (node (ref "E51") (pin "2") (pinfunction "A_2") (pintype "passive"))
      (node (ref "U1") (pin "129") (pinfunction "VREFL0_129") (pintype "input"))
    )
    (net (code "134") (name "/XCIN") (class "Default")
      (node (ref "E22") (pin "1") (pinfunction "A_1") (pintype "passive"))
    )
    (net (code "135") (name "/XCIN_MCU") (class "Default")
      (node (ref "E22") (pin "2") (pinfunction "A_2") (pintype "passive"))
      (node (ref "E25") (pin "2") (pinfunction "A_2") (pintype "passive"))
      (node (ref "U1") (pin "16") (pinfunction "XCIN_16") (pintype "input"))
    )
    (net (code "136") (name "GND") (class "Default")
      (node (ref "C11") (pin "2") (pinfunction "2_2") (pintype "passive"))
      (node (ref "C12") (pin "1") (pinfunction "1_1") (pintype "passive"))
      (node (ref "C13") (pin "1") (pinfunction "1_1") (pintype "passive"))
      (node (ref "C14") (pin "1") (pinfunction "1_1") (pintype "passive"))
      (node (ref "C15") (pin "1") (pinfunction "1_1") (pintype "passive"))
      (node (ref "C16") (pin "1") (pinfunction "1_1") (pintype "passive"))
      (node (ref "C17") (pin "2") (pinfunction "2_2") (pintype "passive"))
      (node (ref "C18") (pin "2") (pinfunction "2_2") (pintype "passive"))
      (node (ref "C4") (pin "1") (pinfunction "1_1") (pintype "passive"))
      (node (ref "C5") (pin "2") (pinfunction "2_2") (pintype "passive"))
      (node (ref "C50") (pin "2") (pinfunction "2_2") (pintype "passive"))
      (node (ref "C51") (pin "2") (pinfunction "2_2") (pintype "passive"))
      (node (ref "C52") (pin "2") (pinfunction "2_2") (pintype "passive"))
      (node (ref "C53") (pin "2") (pinfunction "2_2") (pintype "passive"))
      (node (ref "C54") (pin "2") (pinfunction "2_2") (pintype "passive"))
      (node (ref "C6") (pin "2") (pinfunction "2_2") (pintype "passive"))
      (node (ref "C7") (pin "2") (pinfunction "2_2") (pintype "passive"))
      (node (ref "C9") (pin "2") (pinfunction "2_2") (pintype "passive"))
      (node (ref "E11") (pin "1") (pinfunction "A_1") (pintype "passive"))
      (node (ref "E51") (pin "1") (pinfunction "A_1") (pintype "passive"))
      (node (ref "E53") (pin "1") (pinfunction "A_1") (pintype "passive"))
      (node (ref "U1") (pin "100") (pinfunction "VSS_100") (pintype "power_in"))
      (node (ref "U1") (pin "112") (pinfunction "VSS_112") (pintype "power_in"))
      (node (ref "U1") (pin "122") (pinfunction "VSS_122") (pintype "power_in"))
      (node (ref "U1") (pin "141") (pinfunction "VSS_141") (pintype "power_in"))
      (node (ref "U1") (pin "18") (pinfunction "VSS_18") (pintype "power_in"))
      (node (ref "U1") (pin "37") (pinfunction "VSS_USB_37") (pintype "power_in"))
      (node (ref "U1") (pin "48") (pinfunction "VSS_48") (pintype "power_in"))
      (node (ref "U1") (pin "67") (pinfunction "VSS_67") (pintype "power_in"))
      (node (ref "U1") (pin "82") (pinfunction "VSS_82") (pintype "power_in"))
      (node (ref "U1") (pin "91") (pinfunction "VSS_91") (pintype "power_in"))
    )
    (net (code "137") (name "Net-(C12-Pad2)") (class "Default")
      (node (ref "C12") (pin "2") (pinfunction "2_2") (pintype "passive"))
      (node (ref "E15") (pin "1") (pinfunction "A_1") (pintype "passive"))
    )
    (net (code "138") (name "Net-(C13-Pad2)") (class "Default")
      (node (ref "C13") (pin "2") (pinfunction "2_2") (pintype "passive"))
      (node (ref "E23") (pin "1") (pinfunction "A_1") (pintype "passive"))
      (node (ref "X1") (pin "3") (pinfunction "3_3") (pintype "passive"))
    )
    (net (code "139") (name "Net-(C14-Pad2)") (class "Default")
      (node (ref "C14") (pin "2") (pinfunction "2_2") (pintype "passive"))
      (node (ref "E24") (pin "1") (pinfunction "A_1") (pintype "passive"))
      (node (ref "X1") (pin "1") (pinfunction "1_1") (pintype "passive"))
    )
    (net (code "140") (name "Net-(C15-Pad2)") (class "Default")
      (node (ref "C15") (pin "2") (pinfunction "2_2") (pintype "passive"))
      (node (ref "E25") (pin "1") (pinfunction "A_1") (pintype "passive"))
      (node (ref "X2") (pin "1") (pinfunction "1_1") (pintype "passive"))
    )
    (net (code "141") (name "Net-(C16-Pad2)") (class "Default")
      (node (ref "C16") (pin "2") (pinfunction "2_2") (pintype "passive"))
      (node (ref "E26") (pin "1") (pinfunction "A_1") (pintype "passive"))
      (node (ref "X2") (pin "2") (pinfunction "2_2") (pintype "passive"))
    )
    (net (code "142") (name "Net-(C17-Pad1)") (class "Default")
      (node (ref "C17") (pin "1") (pinfunction "1_1") (pintype "passive"))
      (node (ref "E29") (pin "1") (pinfunction "A_1") (pintype "passive"))
    )
    (net (code "143") (name "Net-(C51-Pad1)") (class "Default")
      (node (ref "C51") (pin "1") (pinfunction "1_1") (pintype "passive"))
      (node (ref "E54") (pin "1") (pinfunction "A_1") (pintype "passive"))
    )
    (net (code "144") (name "Net-(C52-Pad1)") (class "Default")
      (node (ref "C52") (pin "1") (pinfunction "1_1") (pintype "passive"))
      (node (ref "U1") (pin "81") (pinfunction "VCC_81") (pintype "power_in"))
    )
    (net (code "145") (name "Net-(U1-VCL)") (class "Default")
      (node (ref "E54") (pin "2") (pinfunction "A_2") (pintype "passive"))
      (node (ref "E55") (pin "1") (pinfunction "A_1") (pintype "passive"))
      (node (ref "U1") (pin "92") (pinfunction "VCL_92") (pintype "passive"))
    )
    (net (code "146") (name "Net-(U1-VCL0)") (class "Default")
      (node (ref "E28") (pin "2") (pinfunction "A_2") (pintype "passive"))
      (node (ref "E29") (pin "2") (pinfunction "A_2") (pintype "passive"))
      (node (ref "U1") (pin "15") (pinfunction "VCL0_15") (pintype "passive"))
    )
    (net (code "147") (name "Net-(U1-XCOUT)") (class "Default")
      (node (ref "E26") (pin "2") (pinfunction "A_2") (pintype "passive"))
      (node (ref "U1") (pin "17") (pinfunction "XCOUT_17") (pintype "output"))
    )
  )
)
